# Circuit1.net
KiCad netlist of a schematic drawn in Altium Designer
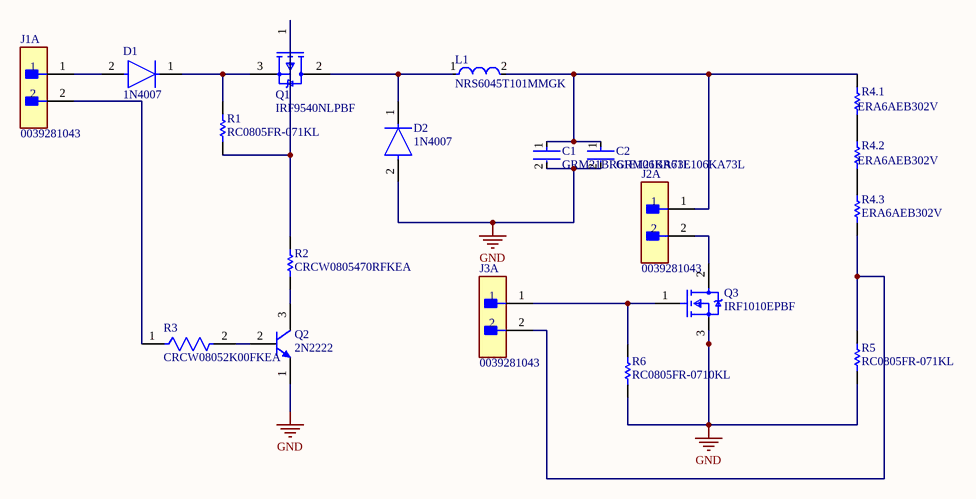
[diagram p0: Circuit1.SchDoc]

(export (version "E")
  (design (tool "Eeschema 10.0.6"))
  (components
    (comp (ref "C1")
      (value "GRM21BR61E106KA73L")
      (footprint "FP-GRM21B-0_15-IPC_C")
      (description "Chip Multilayer Ceramic Capacitors for General Purpose, 0805, 10uF, X5R, 15%, 10%, 25V")
      (fields (field (name "VOLTAGE") "25V") (field (name "TOLERANCE") "10%"))
      (libsource (lib "Altium Content Vault") (part "b4654b650e69147ec39a6b967a45e02"))
    )
    (comp (ref "C2")
      (value "GRM21BR61E106KA73L")
      (footprint "FP-GRM21B-0_15-IPC_C")
      (description "Chip Multilayer Ceramic Capacitors for General Purpose, 0805, 10uF, X5R, 15%, 10%, 25V")
      (fields (field (name "VOLTAGE") "25V") (field (name "TOLERANCE") "10%"))
      (libsource (lib "Altium Content Vault") (part "b4654b650e69147ec39a6b967a45e02"))
    )
    (comp (ref "D1")
      (value "1N4007")
      (footprint "FP-1N4007-MFG")
      (description "Rectifier diode 1000 V 1 A DO-41, ,")
      (fields
        (field (name "MANUFACTURER") "Diotec")
        (field (name "OCTOPART") "https://octopart.com/1n4007-diotec-4040411")
      )
      (libsource (lib "Altium Content Vault") (part "d7152d700b627762746794eb795d46e"))
    )
    (comp (ref "D2")
      (value "1N4007")
      (footprint "FP-1N4007-MFG")
      (description "Rectifier diode 1000 V 1 A DO-41, ,")
      (fields
        (field (name "MANUFACTURER") "Diotec")
        (field (name "OCTOPART") "https://octopart.com/1n4007-diotec-4040411")
      )
      (libsource (lib "Altium Content Vault") (part "d7152d700b627762746794eb795d46e"))
    )
    (comp (ref "J1")
      (value "0039281043")
      (footprint "FP-0039281043-MFG")
      (description "CONN HEADER VERT 4POS 4.2MM")
      (fields
        (field (name "MANUFACTURER") "Molex")
        (field (name "OCTOPART") "https://octopart.com/39-28-1043-molex-7613")
      )
      (libsource (lib "Altium Content Vault") (part "ac72c5313ea981db199dbd0e8237b04"))
    )
    (comp (ref "J2")
      (value "0039281043")
      (footprint "FP-0039281043-MFG")
      (description "CONN HEADER VERT 4POS 4.2MM")
      (fields
        (field (name "MANUFACTURER") "Molex")
        (field (name "OCTOPART") "https://octopart.com/39-28-1043-molex-7613")
      )
      (libsource (lib "Altium Content Vault") (part "ac72c5313ea981db199dbd0e8237b04"))
    )
    (comp (ref "J3")
      (value "0039281043")
      (footprint "FP-0039281043-MFG")
      (description "CONN HEADER VERT 4POS 4.2MM")
      (fields
        (field (name "MANUFACTURER") "Molex")
        (field (name "OCTOPART") "https://octopart.com/39-28-1043-molex-7613")
      )
      (libsource (lib "Altium Content Vault") (part "ac72c5313ea981db199dbd0e8237b04"))
    )
    (comp (ref "L1")
      (value "NRS6045T101MMGK")
      (footprint "FP-NR6045-MFG")
      (description "Shielded Wirewound Inductor 100uH 20% 0.9A 0.6058Ω SMD")
      (fields (field (name "TOLERANCE") "20%"))
      (libsource (lib "Altium Content Vault") (part "725321dda6339637d4d059423bc1c3c"))
    )
    (comp (ref "Q1")
      (value "IRF9540NLPBF")
      (footprint "FP-PG-TO262-3-MFG")
      (description "MOSFET P-CH 100V 23A TO262-3")
      (libsource (lib "Altium Content Vault") (part "38cbee71a1bce1ebb3b8a3a9639eda0"))
    )
    (comp (ref "Q2")
      (value "2N2222")
      (footprint "MLTC-TO-18-3")
      (description "Low Power Bipolar NPN Transistor, 30 V, -65 to 200 degC, 3-Pin TO-18, RoHS, Bulk")
      (fields (field (name "MANUFACTURER") "Multicomp"))
      (libsource (lib "Altium Content Vault") (part "BJT-NPN-EBC-3"))
    )
    (comp (ref "Q3")
      (value "IRF1010EPBF")
      (footprint "FP-PG-TO220-3-MFG")
      (description "MOSFET N-CH 60V 84A TO-220AB")
      (libsource (lib "Altium Content Vault") (part "b09f7f152735e370c1ea22a33fa83d6"))
    )
    (comp (ref "R1")
      (value "RC0805FR-071KL")
      (footprint "RESC2013X60X35ML10T20")
      (description "Chip Resistor, 1 KOhm, +/- 1%, 125 mW, -55 to 155 degC, 0805 (2012 Metric), RoHS, Tape and Reel")
      (fields (field (name "TOLERANCE") "1%") (field (name "MANUFACTURER") "Yageo"))
      (libsource (lib "Altium Content Vault") (part "RES-2"))
    )
    (comp (ref "R2")
      (value "CRCW0805470RFKEA")
      (footprint "RESC2013X50X30LL20T20")
      (fields (field (name "MANUFACTURER") "Vishay Dale"))
      (libsource (lib "Altium Content Vault") (part "RES"))
    )
    (comp (ref "R3")
      (value "CRCW08052K00FKEA")
      (footprint "FP-CRCW0805-e3-IPC_B")
      (description "RES Thick Film, 2kΩ, 1%, 0.125W, 100ppm/°C, 0805")
      (fields (field (name "TOLERANCE") "1%"))
      (libsource (lib "Altium Content Vault") (part "1029c3af85768c4190bb7ad29bc67b5"))
    )
    (comp (ref "R4.1")
      (value "ERA6AEB302V")
      (footprint "RESC2013X60X40LL20T25")
      (fields (field (name "MANUFACTURER") "Panasonic"))
      (libsource (lib "Altium Content Vault") (part "RES"))
    )
    (comp (ref "R4.2")
      (value "ERA6AEB302V")
      (footprint "RESC2013X60X40LL20T25")
      (fields (field (name "MANUFACTURER") "Panasonic"))
      (libsource (lib "Altium Content Vault") (part "RES"))
    )
    (comp (ref "R4.3")
      (value "ERA6AEB302V")
      (footprint "RESC2013X60X40LL20T25")
      (fields (field (name "MANUFACTURER") "Panasonic"))
      (libsource (lib "Altium Content Vault") (part "RES"))
    )
    (comp (ref "R5")
      (value "RC0805FR-071KL")
      (footprint "RESC2013X60X35ML10T20")
      (description "Chip Resistor, 1 KOhm, +/- 1%, 125 mW, -55 to 155 degC, 0805 (2012 Metric), RoHS, Tape and Reel")
      (fields (field (name "TOLERANCE") "1%") (field (name "MANUFACTURER") "Yageo"))
      (libsource (lib "Altium Content Vault") (part "RES-2"))
    )
    (comp (ref "R6")
      (value "RC0805FR-0710KL")
      (footprint "RESC2013X60X35NL10T20")
      (description "Chip Resistor, 10 KOhm, +/- 1%, 0.125 W, -55 to 155 degC, 0805 (2012 Metric), RoHS, Tape and Reel")
      (fields (field (name "MANUFACTURER") "Yageo"))
      (libsource (lib "Altium Content Vault") (part "RES-2"))
    )
  )
  (nets
    (net (code "1") (name "GND") (class "Default")
      (node (ref "C1") (pin "2") (pinfunction "2_2") (pintype "passive"))
      (node (ref "C2") (pin "2") (pinfunction "2_2") (pintype "passive"))
      (node (ref "D2") (pin "2") (pinfunction "A_2") (pintype "passive"))
      (node (ref "Q2") (pin "1") (pinfunction "E_1") (pintype "passive"))
      (node (ref "Q3") (pin "3") (pinfunction "S_3") (pintype "passive"))
      (node (ref "R5") (pin "2") (pinfunction "2_2") (pintype "passive"))
      (node (ref "R6") (pin "2") (pinfunction "2_2") (pintype "passive"))
    )
    (net (code "2") (name "Net-(C1-Pad1)") (class "Default")
      (node (ref "C1") (pin "1") (pinfunction "1_1") (pintype "passive"))
      (node (ref "C2") (pin "1") (pinfunction "1_1") (pintype "passive"))
      (node (ref "J2") (pin "1") (pinfunction "1_1") (pintype "passive"))
      (node (ref "L1") (pin "2") (pinfunction "2_2") (pintype "passive"))
      (node (ref "R4.1") (pin "1") (pinfunction "1_1") (pintype "passive"))
    )
    (net (code "3") (name "Net-(D1-A)") (class "Default")
      (node (ref "D1") (pin "2") (pinfunction "A_2") (pintype "passive"))
      (node (ref "J1") (pin "1") (pinfunction "1_1") (pintype "passive"))
    )
    (net (code "4") (name "Net-(D1-C)") (class "Default")
      (node (ref "D1") (pin "1") (pinfunction "C_1") (pintype "passive"))
      (node (ref "Q1") (pin "3") (pinfunction "Source_3") (pintype "passive"))
      (node (ref "R1") (pin "1") (pinfunction "1_1") (pintype "passive"))
    )
    (net (code "5") (name "Net-(D2-C)") (class "Default")
      (node (ref "D2") (pin "1") (pinfunction "C_1") (pintype "passive"))
      (node (ref "L1") (pin "1") (pinfunction "1_1") (pintype "passive"))
      (node (ref "Q1") (pin "2") (pinfunction "Drain_2") (pintype "passive"))
    )
    (net (code "6") (name "Net-(J1-Pad2)") (class "Default")
      (node (ref "J1") (pin "2") (pinfunction "2_2") (pintype "passive"))
      (node (ref "R3") (pin "1") (pinfunction "1_1") (pintype "passive"))
    )
    (net (code "7") (name "Net-(J3-Pad2)") (class "Default")
      (node (ref "J3") (pin "2") (pinfunction "2_2") (pintype "passive"))
      (node (ref "R4.3") (pin "2") (pinfunction "2_2") (pintype "passive"))
      (node (ref "R5") (pin "1") (pinfunction "1_1") (pintype "passive"))
    )
    (net (code "8") (name "Net-(Q1-Gate)") (class "Default")
      (node (ref "Q1") (pin "1") (pinfunction "Gate_1") (pintype "passive"))
      (node (ref "R1") (pin "2") (pinfunction "2_2") (pintype "passive"))
      (node (ref "R2") (pin "1") (pinfunction "1_1") (pintype "passive"))
    )
    (net (code "9") (name "Net-(Q2-B)") (class "Default")
      (node (ref "Q2") (pin "2") (pinfunction "B_2") (pintype "passive"))
      (node (ref "R3") (pin "2") (pinfunction "2_2") (pintype "passive"))
    )
    (net (code "10") (name "Net-(Q2-C)") (class "Default")
      (node (ref "Q2") (pin "3") (pinfunction "C_3") (pintype "passive"))
      (node (ref "R2") (pin "2") (pinfunction "2_2") (pintype "passive"))
    )
    (net (code "11") (name "Net-(Q3-D)") (class "Default")
      (node (ref "J2") (pin "2") (pinfunction "2_2") (pintype "passive"))
      (node (ref "Q3") (pin "2") (pinfunction "D_2") (pintype "passive"))
    )
    (net (code "12") (name "Net-(Q3-G)") (class "Default")
      (node (ref "J3") (pin "1") (pinfunction "1_1") (pintype "passive"))
      (node (ref "Q3") (pin "1") (pinfunction "G_1") (pintype "passive"))
      (node (ref "R6") (pin "1") (pinfunction "1_1") (pintype "passive"))
    )
    (net (code "13") (name "Net-(R4.1-Pad2)") (class "Default")
      (node (ref "R4.1") (pin "2") (pinfunction "2_2") (pintype "passive"))
      (node (ref "R4.2") (pin "1") (pinfunction "1_1") (pintype "passive"))
    )
    (net (code "14") (name "Net-(R4.2-Pad2)") (class "Default")
      (node (ref "R4.2") (pin "2") (pinfunction "2_2") (pintype "passive"))
      (node (ref "R4.3") (pin "1") (pinfunction "1_1") (pintype "passive"))
    )
  )
)
